# 05_POWER.net
KiCad netlist of a schematic drawn in Altium Designer
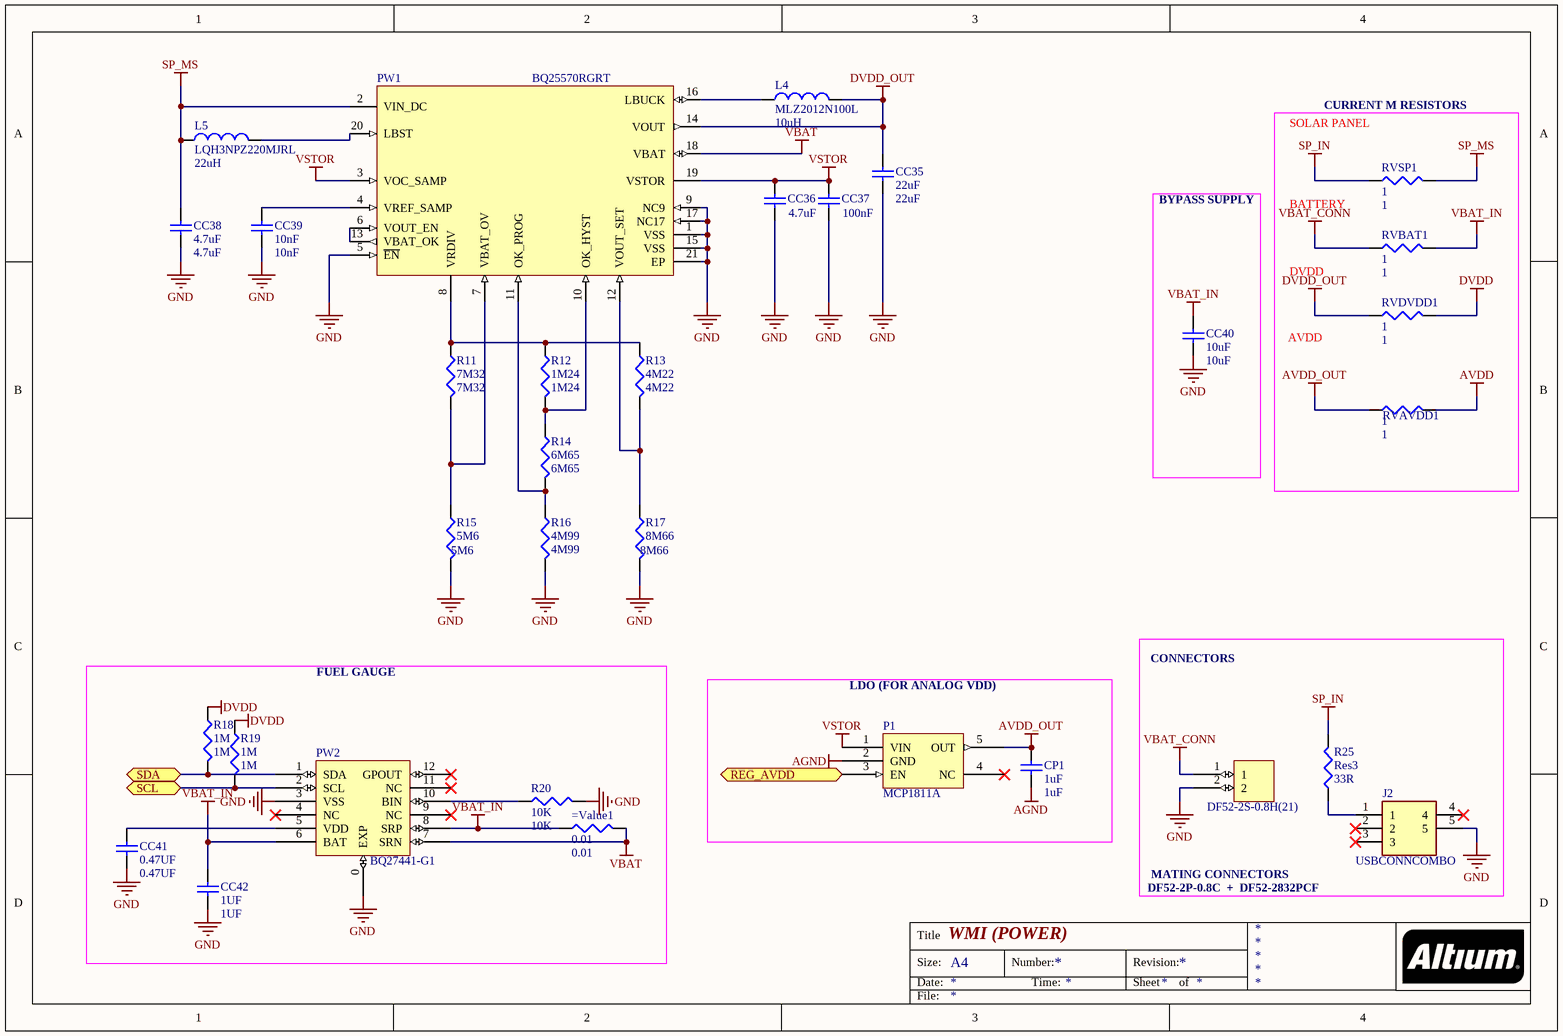
[diagram p0: 05_POWER.SchDoc]

(export (version "E")
  (design (tool "Eeschema 10.0.6"))
  (components
    (comp (ref "=Value1")
      (value "0.01")
      (footprint "0402")
      (description "Resistor")
      (fields (field (name "ALTIUM_VALUE") "0.01") (field (name "PUBLISHER") "Altium Limited"))
      (libsource (lib "Miscellaneous Devices") (part "Res3"))
    )
    (comp (ref "CC35")
      (value "22uF")
      (footprint "J1-0603")
      (description "Capacitor (Semiconductor SIM Model)")
      (fields (field (name "ALTIUM_VALUE") "22uF") (field (name "PUBLISHER") "Altium Limited"))
      (libsource (lib "Miscellaneous Devices") (part "Cap Semi"))
    )
    (comp (ref "CC36")
      (value "4.7uF")
      (footprint "0402")
      (description "Capacitor (Semiconductor SIM Model)")
      (fields (field (name "PUBLISHER") "Altium Limited"))
      (libsource (lib "Miscellaneous Devices") (part "Cap Semi"))
    )
    (comp (ref "CC37")
      (value "100nF")
      (footprint "0603")
      (description "Capacitor (Semiconductor SIM Model)")
      (fields (field (name "PUBLISHER") "Altium Limited"))
      (libsource (lib "Miscellaneous Devices") (part "Cap Semi"))
    )
    (comp (ref "CC38")
      (value "4.7uF")
      (footprint "0402")
      (description "Capacitor (Semiconductor SIM Model)")
      (fields (field (name "ALTIUM_VALUE") "4.7uF") (field (name "PUBLISHER") "Altium Limited"))
      (libsource (lib "Miscellaneous Devices") (part "Cap Semi"))
    )
    (comp (ref "CC39")
      (value "10nF")
      (footprint "J1-0603")
      (description "Capacitor (Semiconductor SIM Model)")
      (fields (field (name "ALTIUM_VALUE") "10nF") (field (name "PUBLISHER") "Altium Limited"))
      (libsource (lib "Miscellaneous Devices") (part "Cap Semi"))
    )
    (comp (ref "CC40")
      (value "10uF")
      (footprint "0402")
      (description "Capacitor (Semiconductor SIM Model)")
      (fields (field (name "ALTIUM_VALUE") "10uF") (field (name "PUBLISHER") "Altium Limited"))
      (libsource (lib "Miscellaneous Devices") (part "Cap Semi"))
    )
    (comp (ref "CC41")
      (value "0.47UF")
      (footprint "0402")
      (description "Capacitor (Semiconductor SIM Model)")
      (fields (field (name "ALTIUM_VALUE") "0.47UF") (field (name "PUBLISHER") "Altium Limited"))
      (libsource (lib "Miscellaneous Devices") (part "Cap Semi"))
    )
    (comp (ref "CC42")
      (value "1UF")
      (footprint "0402")
      (description "Capacitor (Semiconductor SIM Model)")
      (fields (field (name "ALTIUM_VALUE") "1UF") (field (name "PUBLISHER") "Altium Limited"))
      (libsource (lib "Miscellaneous Devices") (part "Cap Semi"))
    )
    (comp (ref "CONN_BAT1")
      (value "DF52-2S-0.8H(21)")
      (footprint "DF52-2S-0.8H(21)")
      (libsource (lib "Schlib1") (part "DF52-2S-0.8H(21)"))
    )
    (comp (ref "CP1")
      (value "1uF")
      (footprint "0402")
      (description "Capacitor (Semiconductor SIM Model)")
      (fields (field (name "ALTIUM_VALUE") "1uF") (field (name "PUBLISHER") "Altium Limited"))
      (libsource (lib "Miscellaneous Devices") (part "Cap Semi"))
    )
    (comp (ref "J2")
      (value "USBCONNCOMBO")
      (footprint "MICRO-USB(2.0-SMT-TYPE-B) Combo 3D")
      (description "Connector")
      (fields
        (field (name "MOUSER2 PART NUMBER") "710-629105136821")
        (field (name "MANUFACTURER_PART_NUMBER") "629105136821")
      )
      (libsource (lib "libUSBConn") (part "629105136821"))
    )
    (comp (ref "L4")
      (value "MLZ2012N100L")
      (footprint "6-0805_N")
      (description "Inductor")
      (fields (field (name "ALTIUM_VALUE") "10uH") (field (name "PUBLISHER") "Altium Limited"))
      (libsource (lib "Miscellaneous Devices") (part "Inductor"))
    )
    (comp (ref "L5")
      (value "LQH3NPZ220MJRL")
      (footprint "1212_PCK")
      (description "Inductor")
      (fields (field (name "ALTIUM_VALUE") "22uH") (field (name "PUBLISHER") "Altium Limited"))
      (libsource (lib "Miscellaneous Devices") (part "Inductor"))
    )
    (comp (ref "P1")
      (value "MCP1811A")
      (footprint "AD Power Mgt Voltage Reference:UJ-5_N")
      (description "Regulator")
      (libsource (lib "Schlib1") (part "MCP1811A"))
    )
    (comp (ref "PW1")
      (value "BQ25570RGRT")
      (footprint "VQFN20")
      (description "IC ENERGY HARV CTRLR BATT 20VQFN")
      (fields (field (name "MANUFACTURER") "Texas Instruments"))
      (libsource (lib "Schlib1") (part "BQ25570RGRT"))
    )
    (comp (ref "PW2")
      (value "BQ27441-G1")
      (footprint "DRZ12_SMALL")
      (libsource (lib "Schlib1") (part "BQ27441-G1"))
    )
    (comp (ref "R11")
      (value "7M32")
      (footprint "0402")
      (description "Resistor")
      (fields (field (name "ALTIUM_VALUE") "7M32") (field (name "PUBLISHER") "Altium Limited"))
      (libsource (lib "Miscellaneous Devices") (part "Res3"))
    )
    (comp (ref "R12")
      (value "1M24")
      (footprint "0402")
      (description "Resistor")
      (fields (field (name "ALTIUM_VALUE") "1M24") (field (name "PUBLISHER") "Altium Limited"))
      (libsource (lib "Miscellaneous Devices") (part "Res3"))
    )
    (comp (ref "R13")
      (value "4M22")
      (footprint "0402")
      (description "Resistor")
      (fields (field (name "ALTIUM_VALUE") "4M22") (field (name "PUBLISHER") "Altium Limited"))
      (libsource (lib "Miscellaneous Devices") (part "Res3"))
    )
    (comp (ref "R14")
      (value "6M65")
      (footprint "0402")
      (description "Resistor")
      (fields (field (name "ALTIUM_VALUE") "6M65") (field (name "PUBLISHER") "Altium Limited"))
      (libsource (lib "Miscellaneous Devices") (part "Res3"))
    )
    (comp (ref "R15")
      (value "5M6")
      (footprint "0402")
      (description "Resistor")
      (fields (field (name "ALTIUM_VALUE") "5M6") (field (name "PUBLISHER") "Altium Limited"))
      (libsource (lib "Miscellaneous Devices") (part "Res3"))
    )
    (comp (ref "R16")
      (value "4M99")
      (footprint "0402")
      (description "Resistor")
      (fields (field (name "ALTIUM_VALUE") "4M99") (field (name "PUBLISHER") "Altium Limited"))
      (libsource (lib "Miscellaneous Devices") (part "Res3"))
    )
    (comp (ref "R17")
      (value "8M66")
      (footprint "0402")
      (description "Resistor")
      (fields (field (name "ALTIUM_VALUE") "8M66") (field (name "PUBLISHER") "Altium Limited"))
      (libsource (lib "Miscellaneous Devices") (part "Res3"))
    )
    (comp (ref "R18")
      (value "1M")
      (footprint "0402")
      (description "Resistor")
      (fields (field (name "ALTIUM_VALUE") "1M") (field (name "PUBLISHER") "Altium Limited"))
      (libsource (lib "Miscellaneous Devices") (part "Res3"))
    )
    (comp (ref "R19")
      (value "1M")
      (footprint "0402")
      (description "Resistor")
      (fields (field (name "ALTIUM_VALUE") "1M") (field (name "PUBLISHER") "Altium Limited"))
      (libsource (lib "Miscellaneous Devices") (part "Res3"))
    )
    (comp (ref "R20")
      (value "10K")
      (footprint "0402")
      (description "Resistor")
      (fields (field (name "ALTIUM_VALUE") "10K") (field (name "PUBLISHER") "Altium Limited"))
      (libsource (lib "Miscellaneous Devices") (part "Res3"))
    )
    (comp (ref "R25")
      (value "Res3")
      (footprint "J1-0603")
      (description "Resistor")
      (fields (field (name "ALTIUM_VALUE") "33R") (field (name "PUBLISHER") "Altium Limited"))
      (libsource (lib "Miscellaneous Devices") (part "Res3"))
    )
    (comp (ref "RVAVDD1")
      (value "1")
      (footprint "J1-0603")
      (description "Resistor")
      (fields (field (name "ALTIUM_VALUE") "1") (field (name "PUBLISHER") "Altium Limited"))
      (libsource (lib "Miscellaneous Devices") (part "Res3"))
    )
    (comp (ref "RVBAT1")
      (value "1")
      (footprint "J1-0603")
      (description "Resistor")
      (fields (field (name "ALTIUM_VALUE") "1") (field (name "PUBLISHER") "Altium Limited"))
      (libsource (lib "Miscellaneous Devices") (part "Res3"))
    )
    (comp (ref "RVDVDD1")
      (value "1")
      (footprint "J1-0603")
      (description "Resistor")
      (fields (field (name "ALTIUM_VALUE") "1") (field (name "PUBLISHER") "Altium Limited"))
      (libsource (lib "Miscellaneous Devices") (part "Res3"))
    )
    (comp (ref "RVSP1")
      (value "1")
      (footprint "J1-0603")
      (description "Resistor")
      (fields (field (name "ALTIUM_VALUE") "1") (field (name "PUBLISHER") "Altium Limited"))
      (libsource (lib "Miscellaneous Devices") (part "Res3"))
    )
  )
  (nets
    (net (code "1") (name "/REG_AVDD") (class "Default")
      (node (ref "P1") (pin "3") (pinfunction "EN_3") (pintype "input"))
    )
    (net (code "2") (name "/SCL") (class "Default")
      (node (ref "PW2") (pin "2") (pinfunction "SCL_2") (pintype "bidirectional"))
      (node (ref "R19") (pin "2") (pinfunction "2_2") (pintype "passive"))
    )
    (net (code "3") (name "/SDA") (class "Default")
      (node (ref "PW2") (pin "1") (pinfunction "SDA_1") (pintype "bidirectional"))
      (node (ref "R18") (pin "2") (pinfunction "2_2") (pintype "passive"))
    )
    (net (code "4") (name "AGND") (class "Default")
      (node (ref "CP1") (pin "1") (pinfunction "1_1") (pintype "passive"))
      (node (ref "P1") (pin "2") (pinfunction "GND_2") (pintype "power_in"))
    )
    (net (code "5") (name "AVDD") (class "Default")
      (node (ref "RVAVDD1") (pin "2") (pinfunction "2_2") (pintype "passive"))
    )
    (net (code "6") (name "AVDD_OUT") (class "Default")
      (node (ref "CP1") (pin "2") (pinfunction "2_2") (pintype "passive"))
      (node (ref "P1") (pin "5") (pinfunction "OUT_5") (pintype "output"))
      (node (ref "RVAVDD1") (pin "1") (pinfunction "1_1") (pintype "passive"))
    )
    (net (code "7") (name "DVDD") (class "Default")
      (node (ref "R18") (pin "1") (pinfunction "1_1") (pintype "passive"))
      (node (ref "R19") (pin "1") (pinfunction "1_1") (pintype "passive"))
      (node (ref "RVDVDD1") (pin "2") (pinfunction "2_2") (pintype "passive"))
    )
    (net (code "8") (name "DVDD_OUT") (class "Default")
      (node (ref "CC35") (pin "2") (pinfunction "2_2") (pintype "passive"))
      (node (ref "L4") (pin "2") (pinfunction "2_2") (pintype "passive"))
      (node (ref "PW1") (pin "14") (pinfunction "VOUT_14") (pintype "output"))
      (node (ref "RVDVDD1") (pin "1") (pinfunction "1_1") (pintype "passive"))
    )
    (net (code "9") (name "GND") (class "Default")
      (node (ref "CC35") (pin "1") (pinfunction "1_1") (pintype "passive"))
      (node (ref "CC36") (pin "1") (pinfunction "1_1") (pintype "passive"))
      (node (ref "CC37") (pin "1") (pinfunction "1_1") (pintype "passive"))
      (node (ref "CC38") (pin "1") (pinfunction "1_1") (pintype "passive"))
      (node (ref "CC39") (pin "1") (pinfunction "1_1") (pintype "passive"))
      (node (ref "CC40") (pin "1") (pinfunction "1_1") (pintype "passive"))
      (node (ref "CC41") (pin "1") (pinfunction "1_1") (pintype "passive"))
      (node (ref "CC42") (pin "1") (pinfunction "1_1") (pintype "passive"))
      (node (ref "CONN_BAT1") (pin "2") (pinfunction "2_2") (pintype "bidirectional"))
      (node (ref "J2") (pin "5") (pinfunction "5_5") (pintype "passive"))
      (node (ref "PW1") (pin "1") (pinfunction "VSS_1") (pintype "power_in"))
      (node (ref "PW1") (pin "15") (pinfunction "VSS_15") (pintype "power_in"))
      (node (ref "PW1") (pin "17") (pinfunction "NC17_17") (pintype "input"))
      (node (ref "PW1") (pin "21") (pinfunction "EP_21") (pintype "passive"))
      (node (ref "PW1") (pin "5") (pinfunction "~{EN}_5") (pintype "input"))
      (node (ref "PW1") (pin "9") (pinfunction "NC9_9") (pintype "input"))
      (node (ref "PW2") (pin "0") (pinfunction "EXP_0") (pintype "bidirectional"))
      (node (ref "PW2") (pin "3") (pinfunction "VSS_3") (pintype "power_in"))
      (node (ref "R15") (pin "2") (pinfunction "2_2") (pintype "passive"))
      (node (ref "R16") (pin "2") (pinfunction "2_2") (pintype "passive"))
      (node (ref "R17") (pin "2") (pinfunction "2_2") (pintype "passive"))
      (node (ref "R20") (pin "2") (pinfunction "2_2") (pintype "passive"))
    )
    (net (code "10") (name "Net-(J2-Pad1)") (class "Default")
      (node (ref "J2") (pin "1") (pinfunction "1_1") (pintype "passive"))
      (node (ref "R25") (pin "1") (pinfunction "1_1") (pintype "passive"))
    )
    (net (code "11") (name "Net-(PW1-LBST)") (class "Default")
      (node (ref "L5") (pin "2") (pinfunction "2_2") (pintype "passive"))
      (node (ref "PW1") (pin "20") (pinfunction "LBST_20") (pintype "input"))
    )
    (net (code "12") (name "Net-(PW1-LBUCK)") (class "Default")
      (node (ref "L4") (pin "1") (pinfunction "1_1") (pintype "passive"))
      (node (ref "PW1") (pin "16") (pinfunction "LBUCK_16") (pintype "bidirectional"))
    )
    (net (code "13") (name "Net-(PW1-OK_HYST)") (class "Default")
      (node (ref "PW1") (pin "10") (pinfunction "OK_HYST_10") (pintype "input"))
      (node (ref "R12") (pin "2") (pinfunction "2_2") (pintype "passive"))
      (node (ref "R14") (pin "1") (pinfunction "1_1") (pintype "passive"))
    )
    (net (code "14") (name "Net-(PW1-OK_PROG)") (class "Default")
      (node (ref "PW1") (pin "11") (pinfunction "OK_PROG_11") (pintype "input"))
      (node (ref "R14") (pin "2") (pinfunction "2_2") (pintype "passive"))
      (node (ref "R16") (pin "1") (pinfunction "1_1") (pintype "passive"))
    )
    (net (code "15") (name "Net-(PW1-VBAT_OK)") (class "Default")
      (node (ref "PW1") (pin "13") (pinfunction "VBAT_OK_13") (pintype "output"))
      (node (ref "PW1") (pin "6") (pinfunction "VOUT_EN_6") (pintype "input"))
    )
    (net (code "16") (name "Net-(PW1-VBAT_OV)") (class "Default")
      (node (ref "PW1") (pin "7") (pinfunction "VBAT_OV_7") (pintype "input"))
      (node (ref "R11") (pin "2") (pinfunction "2_2") (pintype "passive"))
      (node (ref "R15") (pin "1") (pinfunction "1_1") (pintype "passive"))
    )
    (net (code "17") (name "Net-(PW1-VOUT_SET)") (class "Default")
      (node (ref "PW1") (pin "12") (pinfunction "VOUT_SET_12") (pintype "input"))
      (node (ref "R13") (pin "2") (pinfunction "2_2") (pintype "passive"))
      (node (ref "R17") (pin "1") (pinfunction "1_1") (pintype "passive"))
    )
    (net (code "18") (name "Net-(PW1-VRDIV)") (class "Default")
      (node (ref "PW1") (pin "8") (pinfunction "VRDIV_8") (pintype "power_in"))
      (node (ref "R11") (pin "1") (pinfunction "1_1") (pintype "passive"))
      (node (ref "R12") (pin "1") (pinfunction "1_1") (pintype "passive"))
      (node (ref "R13") (pin "1") (pinfunction "1_1") (pintype "passive"))
    )
    (net (code "19") (name "Net-(PW1-VREF_SAMP)") (class "Default")
      (node (ref "CC39") (pin "2") (pinfunction "2_2") (pintype "passive"))
      (node (ref "PW1") (pin "4") (pinfunction "VREF_SAMP_4") (pintype "input"))
    )
    (net (code "20") (name "Net-(PW2-BIN)") (class "Default")
      (node (ref "PW2") (pin "10") (pinfunction "BIN_10") (pintype "bidirectional"))
      (node (ref "R20") (pin "1") (pinfunction "1_1") (pintype "passive"))
    )
    (net (code "21") (name "Net-(PW2-VDD)") (class "Default")
      (node (ref "CC41") (pin "2") (pinfunction "2_2") (pintype "passive"))
      (node (ref "PW2") (pin "5") (pinfunction "VDD_5") (pintype "power_in"))
    )
    (net (code "22") (name "SP_IN") (class "Default")
      (node (ref "R25") (pin "2") (pinfunction "2_2") (pintype "passive"))
      (node (ref "RVSP1") (pin "1") (pinfunction "1_1") (pintype "passive"))
    )
    (net (code "23") (name "SP_MS") (class "Default")
      (node (ref "CC38") (pin "2") (pinfunction "2_2") (pintype "passive"))
      (node (ref "L5") (pin "1") (pinfunction "1_1") (pintype "passive"))
      (node (ref "PW1") (pin "2") (pinfunction "VIN_DC_2") (pintype "power_in"))
      (node (ref "RVSP1") (pin "2") (pinfunction "2_2") (pintype "passive"))
    )
    (net (code "24") (name "VBAT") (class "Default")
      (node (ref "=Value1") (pin "2") (pinfunction "2_2") (pintype "passive"))
      (node (ref "PW1") (pin "18") (pinfunction "VBAT_18") (pintype "bidirectional"))
      (node (ref "PW2") (pin "7") (pinfunction "SRN_7") (pintype "bidirectional"))
    )
    (net (code "25") (name "VBAT_CONN") (class "Default")
      (node (ref "CONN_BAT1") (pin "1") (pinfunction "1_1") (pintype "bidirectional"))
      (node (ref "RVBAT1") (pin "1") (pinfunction "1_1") (pintype "passive"))
    )
    (net (code "26") (name "VBAT_IN") (class "Default")
      (node (ref "=Value1") (pin "1") (pinfunction "1_1") (pintype "passive"))
      (node (ref "CC40") (pin "2") (pinfunction "2_2") (pintype "passive"))
      (node (ref "CC42") (pin "2") (pinfunction "2_2") (pintype "passive"))
      (node (ref "PW2") (pin "6") (pinfunction "BAT_6") (pintype "power_in"))
      (node (ref "PW2") (pin "8") (pinfunction "SRP_8") (pintype "bidirectional"))
      (node (ref "RVBAT1") (pin "2") (pinfunction "2_2") (pintype "passive"))
    )
    (net (code "27") (name "VSTOR") (class "Default")
      (node (ref "CC36") (pin "2") (pinfunction "2_2") (pintype "passive"))
      (node (ref "CC37") (pin "2") (pinfunction "2_2") (pintype "passive"))
      (node (ref "P1") (pin "1") (pinfunction "VIN_1") (pintype "power_in"))
      (node (ref "PW1") (pin "19") (pinfunction "VSTOR_19") (pintype "power_in"))
      (node (ref "PW1") (pin "3") (pinfunction "VOC_SAMP_3") (pintype "input"))
    )
    (net (code "28") (name "unconnected-(J2-Pad2)") (class "Default")
      (node (ref "J2") (pin "2") (pinfunction "2_2") (pintype "passive+no_connect"))
    )
    (net (code "29") (name "unconnected-(J2-Pad3)") (class "Default")
      (node (ref "J2") (pin "3") (pinfunction "3_3") (pintype "passive+no_connect"))
    )
    (net (code "30") (name "unconnected-(J2-Pad4)") (class "Default")
      (node (ref "J2") (pin "4") (pinfunction "4_4") (pintype "passive+no_connect"))
    )
    (net (code "31") (name "unconnected-(P1-NC-Pad4)") (class "Default")
      (node (ref "P1") (pin "4") (pinfunction "NC_4") (pintype "passive+no_connect"))
    )
    (net (code "32") (name "unconnected-(PW2-GPOUT-Pad12)") (class "Default")
      (node (ref "PW2") (pin "12") (pinfunction "GPOUT_12") (pintype "bidirectional+no_connect"))
    )
    (net (code "33") (name "unconnected-(PW2-NC-Pad4)") (class "Default")
      (node (ref "PW2") (pin "4") (pinfunction "NC_4") (pintype "passive+no_connect"))
    )
    (net (code "34") (name "unconnected-(PW2-NC-Pad9)") (class "Default")
      (node (ref "PW2") (pin "9") (pinfunction "NC_9") (pintype "passive+no_connect"))
    )
    (net (code "35") (name "unconnected-(PW2-NC-Pad11)") (class "Default")
      (node (ref "PW2") (pin "11") (pinfunction "NC_11") (pintype "passive+no_connect"))
    )
  )
)
